# design.net
KiCad netlist of a schematic drawn in Altium Designer
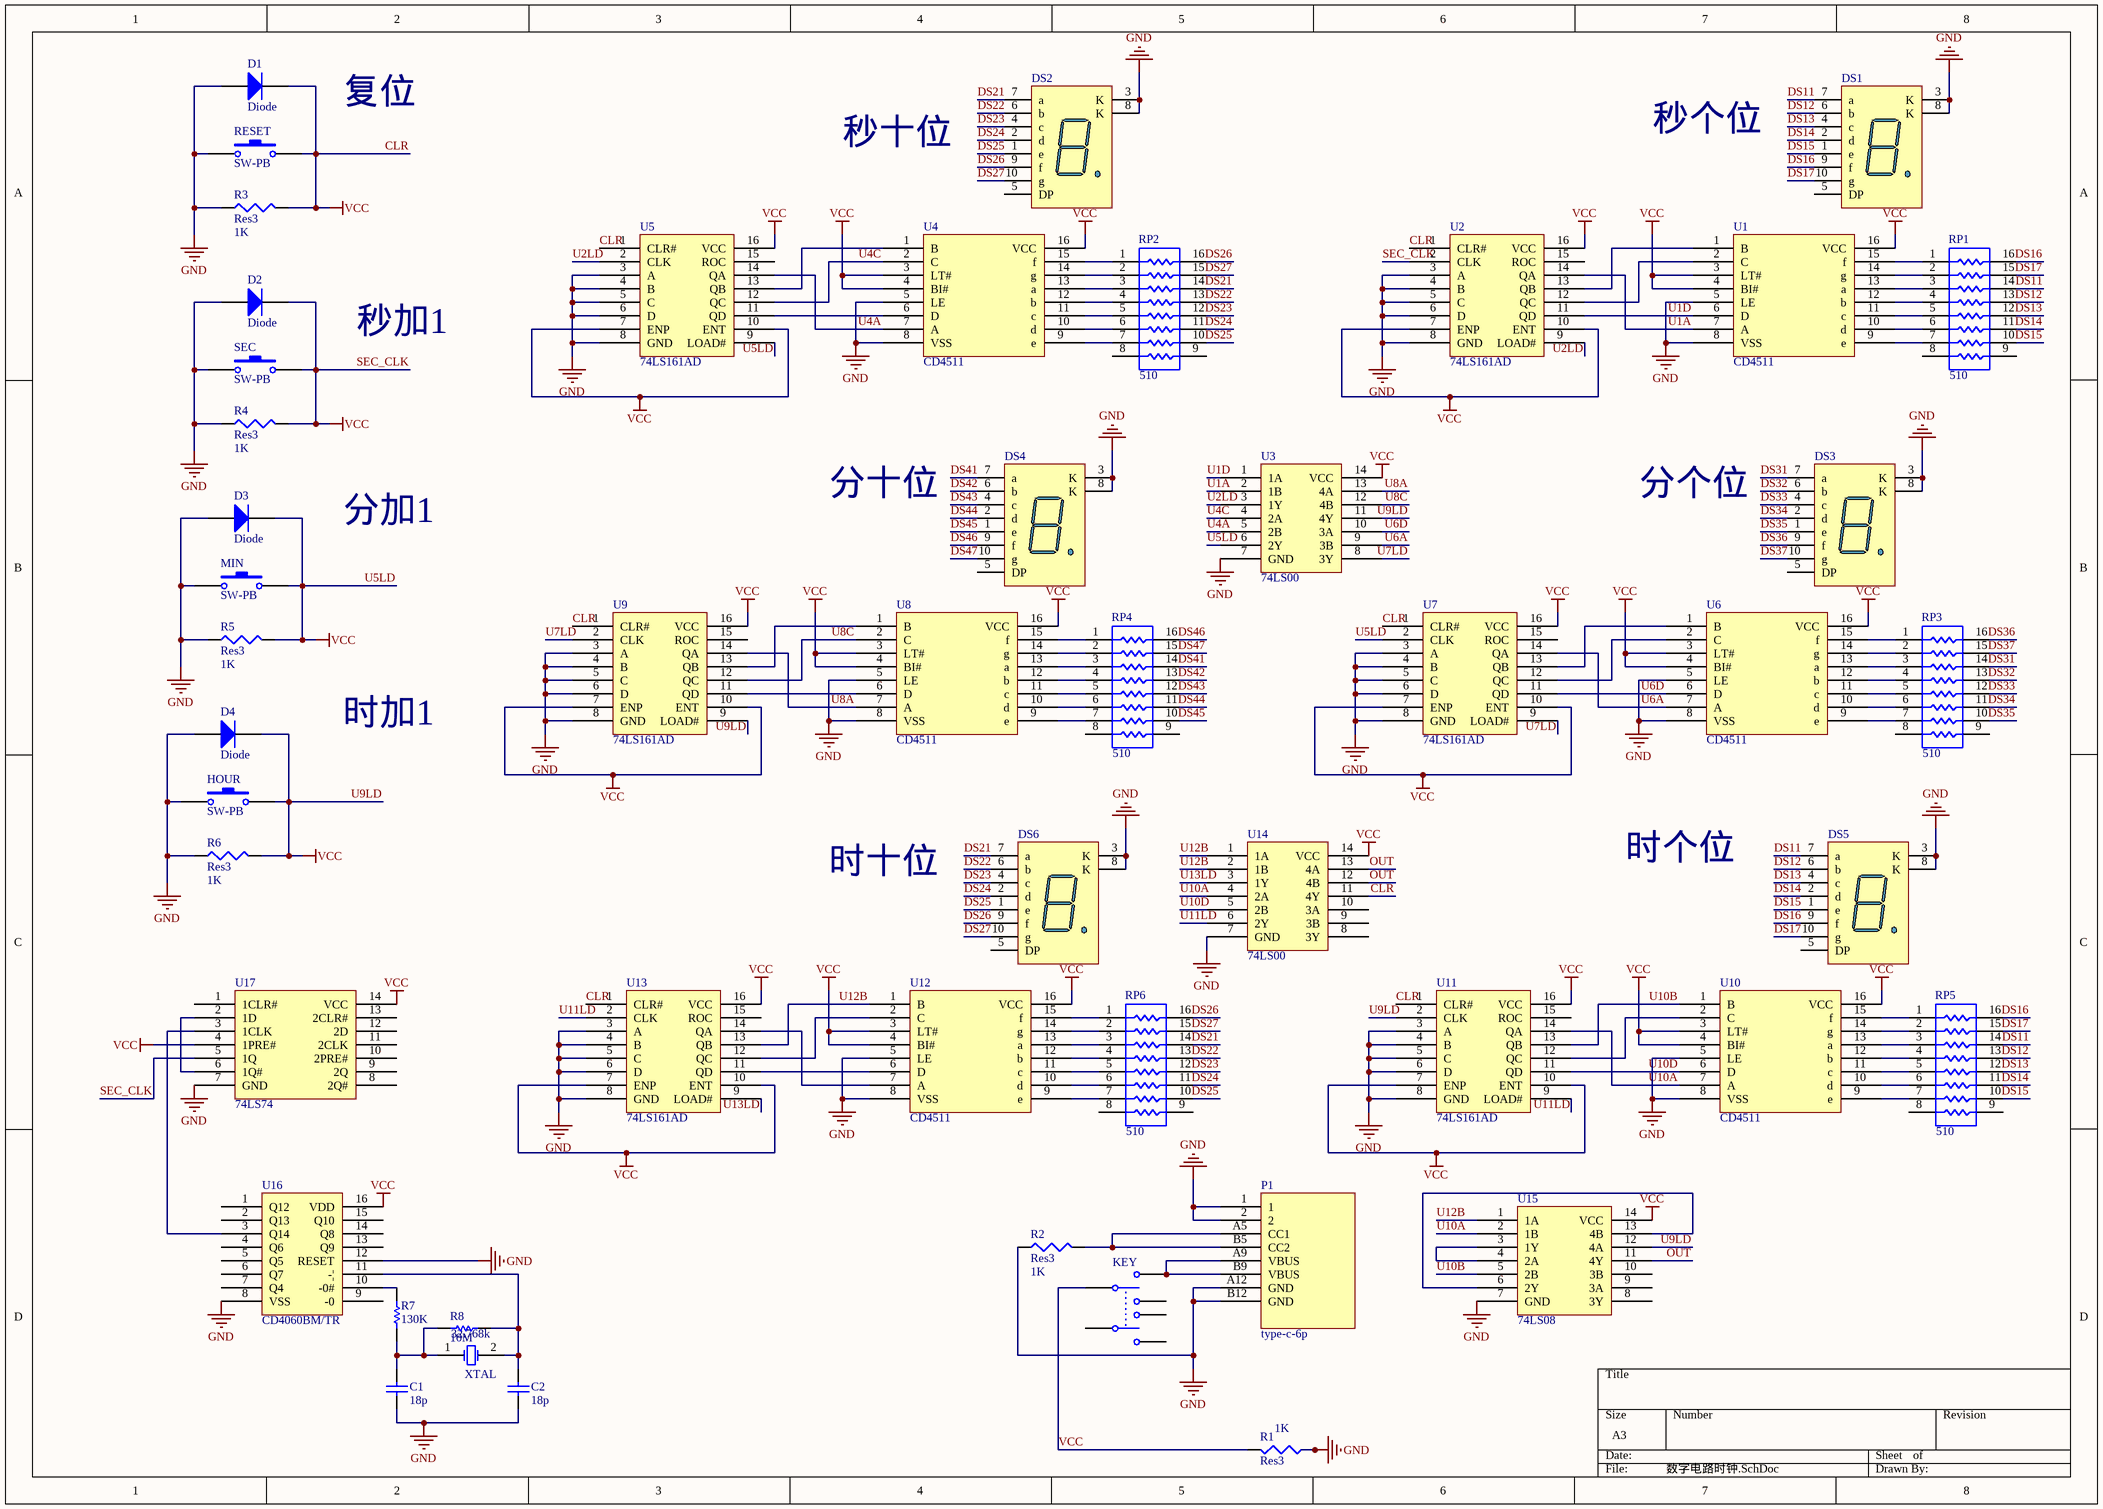
[diagram p0: 数字电路时钟.SchDoc]

(export (version "E")
  (design (tool "Eeschema 10.0.6"))
  (components
    (comp (ref "32.768k")
      (value "XTAL")
      (footprint "R38")
      (description "Crystal Oscillator")
      (fields (field (name "PUBLISHER") "Altium Limited"))
      (libsource (lib "Miscellaneous Devices") (part "XTAL"))
    )
    (comp (ref "C1")
      (value "18p")
      (footprint "C1206")
      (description "Capacitor (Semiconductor SIM Model)")
      (fields (field (name "Comment") "Cap Semi") (field (name "PUBLISHER") "Altium Limited"))
      (libsource (lib "Miscellaneous Devices") (part "Cap Semi"))
    )
    (comp (ref "C2")
      (value "18p")
      (footprint "C1206")
      (description "Capacitor (Semiconductor SIM Model)")
      (fields (field (name "Comment") "Cap Semi") (field (name "PUBLISHER") "Altium Limited"))
      (libsource (lib "Miscellaneous Devices") (part "Cap Semi"))
    )
    (comp (ref "D1")
      (value "Diode")
      (footprint "SMC")
      (description "Default Diode")
      (fields (field (name "PUBLISHER") "Altium Limited"))
      (libsource (lib "Miscellaneous Devices") (part "Diode"))
    )
    (comp (ref "D2")
      (value "Diode")
      (footprint "SMC")
      (description "Default Diode")
      (fields (field (name "PUBLISHER") "Altium Limited"))
      (libsource (lib "Miscellaneous Devices") (part "Diode"))
    )
    (comp (ref "D3")
      (value "Diode")
      (footprint "SMC")
      (description "Default Diode")
      (fields (field (name "PUBLISHER") "Altium Limited"))
      (libsource (lib "Miscellaneous Devices") (part "Diode"))
    )
    (comp (ref "D4")
      (value "Diode")
      (footprint "SMC")
      (description "Default Diode")
      (fields (field (name "PUBLISHER") "Altium Limited"))
      (libsource (lib "Miscellaneous Devices") (part "Diode"))
    )
    (comp (ref "DS1")
      (value "Dpy Blue-CC")
      (footprint "H")
      (description "14.2 mm General Purpose Blue 7-Segment Display: CC, RH DP, Gray Surface")
      (fields (field (name "PUBLISHER") "Altium Limited"))
      (libsource (lib "Miscellaneous Devices") (part "Dpy Blue-CC"))
    )
    (comp (ref "DS2")
      (value "Dpy Blue-CC")
      (footprint "H")
      (description "14.2 mm General Purpose Blue 7-Segment Display: CC, RH DP, Gray Surface")
      (fields (field (name "PUBLISHER") "Altium Limited"))
      (libsource (lib "Miscellaneous Devices") (part "Dpy Blue-CC"))
    )
    (comp (ref "DS3")
      (value "Dpy Blue-CC")
      (footprint "H")
      (description "14.2 mm General Purpose Blue 7-Segment Display: CC, RH DP, Gray Surface")
      (fields (field (name "PUBLISHER") "Altium Limited"))
      (libsource (lib "Miscellaneous Devices") (part "Dpy Blue-CC"))
    )
    (comp (ref "DS4")
      (value "Dpy Blue-CC")
      (footprint "H")
      (description "14.2 mm General Purpose Blue 7-Segment Display: CC, RH DP, Gray Surface")
      (fields (field (name "PUBLISHER") "Altium Limited"))
      (libsource (lib "Miscellaneous Devices") (part "Dpy Blue-CC"))
    )
    (comp (ref "DS5")
      (value "Dpy Blue-CC")
      (footprint "H")
      (description "14.2 mm General Purpose Blue 7-Segment Display: CC, RH DP, Gray Surface")
      (fields (field (name "PUBLISHER") "Altium Limited"))
      (libsource (lib "Miscellaneous Devices") (part "Dpy Blue-CC"))
    )
    (comp (ref "DS6")
      (value "Dpy Blue-CC")
      (footprint "H")
      (description "14.2 mm General Purpose Blue 7-Segment Display: CC, RH DP, Gray Surface")
      (fields (field (name "PUBLISHER") "Altium Limited"))
      (libsource (lib "Miscellaneous Devices") (part "Dpy Blue-CC"))
    )
    (comp (ref "HOUR")
      (value "SW-PB")
      (footprint "SPST-2")
      (description "Switch")
      (fields (field (name "PUBLISHER") "Altium Limited"))
      (libsource (lib "Miscellaneous Devices") (part "SW-PB"))
    )
    (comp (ref "KEY")
      (value "SW-DPDT")
      (footprint "SOT23-6_N")
      (description "Double-Pole, Double-Throw Switch")
      (fields (field (name "PUBLISHER") "Altium Limited"))
      (libsource (lib "Miscellaneous Devices") (part "SW-DPDT"))
    )
    (comp (ref "MIN")
      (value "SW-PB")
      (footprint "SPST-2")
      (description "Switch")
      (fields (field (name "PUBLISHER") "Altium Limited"))
      (libsource (lib "Miscellaneous Devices") (part "SW-PB"))
    )
    (comp (ref "P1")
      (value "type-c-6p")
      (footprint "type-c-6p - duplicate")
      (libsource (lib "数字时钟_课设") (part "type-c-6p"))
    )
    (comp (ref "R1")
      (value "Res3")
      (footprint "J1-0603")
      (description "Resistor")
      (fields (field (name "ALTIUM_VALUE") "1K") (field (name "PUBLISHER") "Altium Limited"))
      (libsource (lib "Miscellaneous Devices") (part "Res3"))
    )
    (comp (ref "R2")
      (value "Res3")
      (footprint "J1-0603")
      (description "Resistor")
      (fields (field (name "ALTIUM_VALUE") "1K") (field (name "PUBLISHER") "Altium Limited"))
      (libsource (lib "Miscellaneous Devices") (part "Res3"))
    )
    (comp (ref "R3")
      (value "Res3")
      (footprint "J1-0603")
      (description "Resistor")
      (fields (field (name "ALTIUM_VALUE") "1K") (field (name "PUBLISHER") "Altium Limited"))
      (libsource (lib "Miscellaneous Devices") (part "Res3"))
    )
    (comp (ref "R4")
      (value "Res3")
      (footprint "J1-0603")
      (description "Resistor")
      (fields (field (name "ALTIUM_VALUE") "1K") (field (name "PUBLISHER") "Altium Limited"))
      (libsource (lib "Miscellaneous Devices") (part "Res3"))
    )
    (comp (ref "R5")
      (value "Res3")
      (footprint "J1-0603")
      (description "Resistor")
      (fields (field (name "ALTIUM_VALUE") "1K") (field (name "PUBLISHER") "Altium Limited"))
      (libsource (lib "Miscellaneous Devices") (part "Res3"))
    )
    (comp (ref "R6")
      (value "Res3")
      (footprint "J1-0603")
      (description "Resistor")
      (fields (field (name "ALTIUM_VALUE") "1K") (field (name "PUBLISHER") "Altium Limited"))
      (libsource (lib "Miscellaneous Devices") (part "Res3"))
    )
    (comp (ref "R7")
      (value "130K")
      (footprint "AXIAL-0.3")
      (description "Resistor")
      (fields (field (name "Comment") "Res1") (field (name "PUBLISHER") "Altium Limited"))
      (libsource (lib "Miscellaneous Devices") (part "Res1"))
    )
    (comp (ref "R8")
      (value "10M")
      (footprint "AXIAL-0.3")
      (description "Resistor")
      (fields (field (name "Comment") "Res1") (field (name "PUBLISHER") "Altium Limited"))
      (libsource (lib "Miscellaneous Devices") (part "Res1"))
    )
    (comp (ref "RESET")
      (value "SW-PB")
      (footprint "SPST-2")
      (description "Switch")
      (fields (field (name "PUBLISHER") "Altium Limited"))
      (libsource (lib "Miscellaneous Devices") (part "SW-PB"))
    )
    (comp (ref "RP1")
      (value "510")
      (footprint "SO-16_N")
      (description "Isolated Resistor Network")
      (fields (field (name "Comment") "Res Pack3") (field (name "PUBLISHER") "Altium Limited"))
      (libsource (lib "Miscellaneous Devices") (part "Res Pack3"))
    )
    (comp (ref "RP2")
      (value "510")
      (footprint "SO-16_N")
      (description "Isolated Resistor Network")
      (fields (field (name "Comment") "Res Pack3") (field (name "PUBLISHER") "Altium Limited"))
      (libsource (lib "Miscellaneous Devices") (part "Res Pack3"))
    )
    (comp (ref "RP3")
      (value "510")
      (footprint "SO-16_N")
      (description "Isolated Resistor Network")
      (fields (field (name "Comment") "Res Pack3") (field (name "PUBLISHER") "Altium Limited"))
      (libsource (lib "Miscellaneous Devices") (part "Res Pack3"))
    )
    (comp (ref "RP4")
      (value "510")
      (footprint "SO-16_N")
      (description "Isolated Resistor Network")
      (fields (field (name "Comment") "Res Pack3") (field (name "PUBLISHER") "Altium Limited"))
      (libsource (lib "Miscellaneous Devices") (part "Res Pack3"))
    )
    (comp (ref "RP5")
      (value "510")
      (footprint "SO-16_N")
      (description "Isolated Resistor Network")
      (fields (field (name "Comment") "Res Pack3") (field (name "PUBLISHER") "Altium Limited"))
      (libsource (lib "Miscellaneous Devices") (part "Res Pack3"))
    )
    (comp (ref "RP6")
      (value "510")
      (footprint "SO-16_N")
      (description "Isolated Resistor Network")
      (fields (field (name "Comment") "Res Pack3") (field (name "PUBLISHER") "Altium Limited"))
      (libsource (lib "Miscellaneous Devices") (part "Res Pack3"))
    )
    (comp (ref "SEC")
      (value "SW-PB")
      (footprint "SPST-2")
      (description "Switch")
      (fields (field (name "PUBLISHER") "Altium Limited"))
      (libsource (lib "Miscellaneous Devices") (part "SW-PB"))
    )
    (comp (ref "U1") (value "CD4511") (footprint "CD4511BM/TR") (libsource (lib "数字电路时钟") (part "CD4511")))
    (comp (ref "U2") (value "74LS161AD") (footprint "74LS161") (libsource (lib "数字电路时钟") (part "74LS161AD")))
    (comp (ref "U3") (value "74LS00") (footprint "74LS00") (libsource (lib "数字电路时钟") (part "74LS00")))
    (comp (ref "U4") (value "CD4511") (footprint "CD4511BM/TR") (libsource (lib "数字电路时钟") (part "CD4511")))
    (comp (ref "U5") (value "74LS161AD") (footprint "74LS161") (libsource (lib "数字电路时钟") (part "74LS161AD")))
    (comp (ref "U6") (value "CD4511") (footprint "CD4511BM/TR") (libsource (lib "数字电路时钟") (part "CD4511")))
    (comp (ref "U7") (value "74LS161AD") (footprint "74LS161") (libsource (lib "数字电路时钟") (part "74LS161AD")))
    (comp (ref "U8") (value "CD4511") (footprint "CD4511BM/TR") (libsource (lib "数字电路时钟") (part "CD4511")))
    (comp (ref "U9") (value "74LS161AD") (footprint "74LS161") (libsource (lib "数字电路时钟") (part "74LS161AD")))
    (comp (ref "U10") (value "CD4511") (footprint "CD4511BM/TR") (libsource (lib "数字电路时钟") (part "CD4511")))
    (comp (ref "U11") (value "74LS161AD") (footprint "74LS161") (libsource (lib "数字电路时钟") (part "74LS161AD")))
    (comp (ref "U12") (value "CD4511") (footprint "CD4511BM/TR") (libsource (lib "数字电路时钟") (part "CD4511")))
    (comp (ref "U13") (value "74LS161AD") (footprint "74LS161") (libsource (lib "数字电路时钟") (part "74LS161AD")))
    (comp (ref "U14") (value "74LS00") (footprint "74LS00") (libsource (lib "数字电路时钟") (part "74LS00")))
    (comp (ref "U15") (value "74LS08") (footprint "74LS08") (libsource (lib "数字电路时钟") (part "74LS08")))
    (comp (ref "U16")
      (value "CD4060BM/TR")
      (footprint "CD4060BM/TR")
      (libsource (lib "数字电路时钟") (part "CD4060BM/TR"))
    )
    (comp (ref "U17") (value "74LS74") (footprint "74LS74") (libsource (lib "数字电路时钟") (part "74LS74")))
  )
  (nets
    (net (code "1") (name "/DS11") (class "Default")
      (node (ref "DS1") (pin "7") (pinfunction "a_7") (pintype "passive"))
      (node (ref "DS5") (pin "7") (pinfunction "a_7") (pintype "passive"))
      (node (ref "RP1") (pin "14") (pinfunction "14_14") (pintype "passive"))
      (node (ref "RP5") (pin "14") (pinfunction "14_14") (pintype "passive"))
    )
    (net (code "2") (name "/DS12") (class "Default")
      (node (ref "DS1") (pin "6") (pinfunction "b_6") (pintype "passive"))
      (node (ref "DS5") (pin "6") (pinfunction "b_6") (pintype "passive"))
      (node (ref "RP1") (pin "13") (pinfunction "13_13") (pintype "passive"))
      (node (ref "RP5") (pin "13") (pinfunction "13_13") (pintype "passive"))
    )
    (net (code "3") (name "/DS13") (class "Default")
      (node (ref "DS1") (pin "4") (pinfunction "c_4") (pintype "passive"))
      (node (ref "DS5") (pin "4") (pinfunction "c_4") (pintype "passive"))
      (node (ref "RP1") (pin "12") (pinfunction "12_12") (pintype "passive"))
      (node (ref "RP5") (pin "12") (pinfunction "12_12") (pintype "passive"))
    )
    (net (code "4") (name "/DS14") (class "Default")
      (node (ref "DS1") (pin "2") (pinfunction "d_2") (pintype "passive"))
      (node (ref "DS5") (pin "2") (pinfunction "d_2") (pintype "passive"))
      (node (ref "RP1") (pin "11") (pinfunction "11_11") (pintype "passive"))
      (node (ref "RP5") (pin "11") (pinfunction "11_11") (pintype "passive"))
    )
    (net (code "5") (name "/DS15") (class "Default")
      (node (ref "DS1") (pin "1") (pinfunction "e_1") (pintype "passive"))
      (node (ref "DS5") (pin "1") (pinfunction "e_1") (pintype "passive"))
      (node (ref "RP1") (pin "10") (pinfunction "10_10") (pintype "passive"))
      (node (ref "RP5") (pin "10") (pinfunction "10_10") (pintype "passive"))
    )
    (net (code "6") (name "/DS16") (class "Default")
      (node (ref "DS1") (pin "9") (pinfunction "f_9") (pintype "passive"))
      (node (ref "DS5") (pin "9") (pinfunction "f_9") (pintype "passive"))
      (node (ref "RP1") (pin "16") (pinfunction "16_16") (pintype "passive"))
      (node (ref "RP5") (pin "16") (pinfunction "16_16") (pintype "passive"))
    )
    (net (code "7") (name "/DS17") (class "Default")
      (node (ref "DS1") (pin "10") (pinfunction "g_10") (pintype "passive"))
      (node (ref "DS5") (pin "10") (pinfunction "g_10") (pintype "passive"))
      (node (ref "RP1") (pin "15") (pinfunction "15_15") (pintype "passive"))
      (node (ref "RP5") (pin "15") (pinfunction "15_15") (pintype "passive"))
    )
    (net (code "8") (name "/DS21") (class "Default")
      (node (ref "DS2") (pin "7") (pinfunction "a_7") (pintype "passive"))
      (node (ref "DS6") (pin "7") (pinfunction "a_7") (pintype "passive"))
      (node (ref "RP2") (pin "14") (pinfunction "14_14") (pintype "passive"))
      (node (ref "RP6") (pin "14") (pinfunction "14_14") (pintype "passive"))
    )
    (net (code "9") (name "/DS22") (class "Default")
      (node (ref "DS2") (pin "6") (pinfunction "b_6") (pintype "passive"))
      (node (ref "DS6") (pin "6") (pinfunction "b_6") (pintype "passive"))
      (node (ref "RP2") (pin "13") (pinfunction "13_13") (pintype "passive"))
      (node (ref "RP6") (pin "13") (pinfunction "13_13") (pintype "passive"))
    )
    (net (code "10") (name "/DS23") (class "Default")
      (node (ref "DS2") (pin "4") (pinfunction "c_4") (pintype "passive"))
      (node (ref "DS6") (pin "4") (pinfunction "c_4") (pintype "passive"))
      (node (ref "RP2") (pin "12") (pinfunction "12_12") (pintype "passive"))
      (node (ref "RP6") (pin "12") (pinfunction "12_12") (pintype "passive"))
    )
    (net (code "11") (name "/DS24") (class "Default")
      (node (ref "DS2") (pin "2") (pinfunction "d_2") (pintype "passive"))
      (node (ref "DS6") (pin "2") (pinfunction "d_2") (pintype "passive"))
      (node (ref "RP2") (pin "11") (pinfunction "11_11") (pintype "passive"))
      (node (ref "RP6") (pin "11") (pinfunction "11_11") (pintype "passive"))
    )
    (net (code "12") (name "/DS25") (class "Default")
      (node (ref "DS2") (pin "1") (pinfunction "e_1") (pintype "passive"))
      (node (ref "DS6") (pin "1") (pinfunction "e_1") (pintype "passive"))
      (node (ref "RP2") (pin "10") (pinfunction "10_10") (pintype "passive"))
      (node (ref "RP6") (pin "10") (pinfunction "10_10") (pintype "passive"))
    )
    (net (code "13") (name "/DS26") (class "Default")
      (node (ref "DS2") (pin "9") (pinfunction "f_9") (pintype "passive"))
      (node (ref "DS6") (pin "9") (pinfunction "f_9") (pintype "passive"))
      (node (ref "RP2") (pin "16") (pinfunction "16_16") (pintype "passive"))
      (node (ref "RP6") (pin "16") (pinfunction "16_16") (pintype "passive"))
    )
    (net (code "14") (name "/DS27") (class "Default")
      (node (ref "DS2") (pin "10") (pinfunction "g_10") (pintype "passive"))
      (node (ref "DS6") (pin "10") (pinfunction "g_10") (pintype "passive"))
      (node (ref "RP2") (pin "15") (pinfunction "15_15") (pintype "passive"))
      (node (ref "RP6") (pin "15") (pinfunction "15_15") (pintype "passive"))
    )
    (net (code "15") (name "/DS31") (class "Default")
      (node (ref "DS3") (pin "7") (pinfunction "a_7") (pintype "passive"))
      (node (ref "RP3") (pin "14") (pinfunction "14_14") (pintype "passive"))
    )
    (net (code "16") (name "/DS32") (class "Default")
      (node (ref "DS3") (pin "6") (pinfunction "b_6") (pintype "passive"))
      (node (ref "RP3") (pin "13") (pinfunction "13_13") (pintype "passive"))
    )
    (net (code "17") (name "/DS33") (class "Default")
      (node (ref "DS3") (pin "4") (pinfunction "c_4") (pintype "passive"))
      (node (ref "RP3") (pin "12") (pinfunction "12_12") (pintype "passive"))
    )
    (net (code "18") (name "/DS34") (class "Default")
      (node (ref "DS3") (pin "2") (pinfunction "d_2") (pintype "passive"))
      (node (ref "RP3") (pin "11") (pinfunction "11_11") (pintype "passive"))
    )
    (net (code "19") (name "/DS35") (class "Default")
      (node (ref "DS3") (pin "1") (pinfunction "e_1") (pintype "passive"))
      (node (ref "RP3") (pin "10") (pinfunction "10_10") (pintype "passive"))
    )
    (net (code "20") (name "/DS36") (class "Default")
      (node (ref "DS3") (pin "9") (pinfunction "f_9") (pintype "passive"))
      (node (ref "RP3") (pin "16") (pinfunction "16_16") (pintype "passive"))
    )
    (net (code "21") (name "/DS37") (class "Default")
      (node (ref "DS3") (pin "10") (pinfunction "g_10") (pintype "passive"))
      (node (ref "RP3") (pin "15") (pinfunction "15_15") (pintype "passive"))
    )
    (net (code "22") (name "/DS41") (class "Default")
      (node (ref "DS4") (pin "7") (pinfunction "a_7") (pintype "passive"))
      (node (ref "RP4") (pin "14") (pinfunction "14_14") (pintype "passive"))
    )
    (net (code "23") (name "/DS42") (class "Default")
      (node (ref "DS4") (pin "6") (pinfunction "b_6") (pintype "passive"))
      (node (ref "RP4") (pin "13") (pinfunction "13_13") (pintype "passive"))
    )
    (net (code "24") (name "/DS43") (class "Default")
      (node (ref "DS4") (pin "4") (pinfunction "c_4") (pintype "passive"))
      (node (ref "RP4") (pin "12") (pinfunction "12_12") (pintype "passive"))
    )
    (net (code "25") (name "/DS44") (class "Default")
      (node (ref "DS4") (pin "2") (pinfunction "d_2") (pintype "passive"))
      (node (ref "RP4") (pin "11") (pinfunction "11_11") (pintype "passive"))
    )
    (net (code "26") (name "/DS45") (class "Default")
      (node (ref "DS4") (pin "1") (pinfunction "e_1") (pintype "passive"))
      (node (ref "RP4") (pin "10") (pinfunction "10_10") (pintype "passive"))
    )
    (net (code "27") (name "/DS46") (class "Default")
      (node (ref "DS4") (pin "9") (pinfunction "f_9") (pintype "passive"))
      (node (ref "RP4") (pin "16") (pinfunction "16_16") (pintype "passive"))
    )
    (net (code "28") (name "/DS47") (class "Default")
      (node (ref "DS4") (pin "10") (pinfunction "g_10") (pintype "passive"))
      (node (ref "RP4") (pin "15") (pinfunction "15_15") (pintype "passive"))
    )
    (net (code "29") (name "/OUT") (class "Default")
      (node (ref "U14") (pin "12") (pinfunction "4B_12") (pintype "passive"))
      (node (ref "U14") (pin "13") (pinfunction "4A_13") (pintype "passive"))
      (node (ref "U15") (pin "11") (pinfunction "4Y_11") (pintype "passive"))
    )
    (net (code "30") (name "/U1A") (class "Default")
      (node (ref "U1") (pin "7") (pinfunction "A_7") (pintype "passive"))
      (node (ref "U2") (pin "14") (pinfunction "QA_14") (pintype "passive"))
      (node (ref "U3") (pin "2") (pinfunction "1B_2") (pintype "passive"))
    )
    (net (code "31") (name "/U1D") (class "Default")
      (node (ref "U1") (pin "6") (pinfunction "D_6") (pintype "passive"))
      (node (ref "U2") (pin "11") (pinfunction "QD_11") (pintype "passive"))
      (node (ref "U3") (pin "1") (pinfunction "1A_1") (pintype "passive"))
    )
    (net (code "32") (name "/U2LD") (class "Default")
      (node (ref "U2") (pin "9") (pinfunction "LOAD#_9") (pintype "passive"))
      (node (ref "U3") (pin "3") (pinfunction "1Y_3") (pintype "passive"))
      (node (ref "U5") (pin "2") (pinfunction "CLK_2") (pintype "passive"))
    )
    (net (code "33") (name "/U4A") (class "Default")
      (node (ref "U3") (pin "5") (pinfunction "2B_5") (pintype "passive"))
      (node (ref "U4") (pin "7") (pinfunction "A_7") (pintype "passive"))
      (node (ref "U5") (pin "14") (pinfunction "QA_14") (pintype "passive"))
    )
    (net (code "34") (name "/U4C") (class "Default")
      (node (ref "U3") (pin "4") (pinfunction "2A_4") (pintype "passive"))
      (node (ref "U4") (pin "2") (pinfunction "C_2") (pintype "passive"))
      (node (ref "U5") (pin "12") (pinfunction "QC_12") (pintype "passive"))
    )
    (net (code "35") (name "/U6A") (class "Default")
      (node (ref "U3") (pin "9") (pinfunction "3B_9") (pintype "passive"))
      (node (ref "U6") (pin "7") (pinfunction "A_7") (pintype "passive"))
      (node (ref "U7") (pin "14") (pinfunction "QA_14") (pintype "passive"))
    )
    (net (code "36") (name "/U6D") (class "Default")
      (node (ref "U3") (pin "10") (pinfunction "3A_10") (pintype "passive"))
      (node (ref "U6") (pin "6") (pinfunction "D_6") (pintype "passive"))
      (node (ref "U7") (pin "11") (pinfunction "QD_11") (pintype "passive"))
    )
    (net (code "37") (name "/U7LD") (class "Default")
      (node (ref "U3") (pin "8") (pinfunction "3Y_8") (pintype "passive"))
      (node (ref "U7") (pin "9") (pinfunction "LOAD#_9") (pintype "passive"))
      (node (ref "U9") (pin "2") (pinfunction "CLK_2") (pintype "passive"))
    )
    (net (code "38") (name "/U8A") (class "Default")
      (node (ref "U3") (pin "13") (pinfunction "4A_13") (pintype "passive"))
      (node (ref "U8") (pin "7") (pinfunction "A_7") (pintype "passive"))
      (node (ref "U9") (pin "14") (pinfunction "QA_14") (pintype "passive"))
    )
    (net (code "39") (name "/U8C") (class "Default")
      (node (ref "U3") (pin "12") (pinfunction "4B_12") (pintype "passive"))
      (node (ref "U8") (pin "2") (pinfunction "C_2") (pintype "passive"))
      (node (ref "U9") (pin "12") (pinfunction "QC_12") (pintype "passive"))
    )
    (net (code "40") (name "/U10A") (class "Default")
      (node (ref "U10") (pin "7") (pinfunction "A_7") (pintype "passive"))
      (node (ref "U11") (pin "14") (pinfunction "QA_14") (pintype "passive"))
      (node (ref "U14") (pin "4") (pinfunction "2A_4") (pintype "passive"))
      (node (ref "U15") (pin "2") (pinfunction "1B_2") (pintype "passive"))
    )
    (net (code "41") (name "/U10B") (class "Default")
      (node (ref "U10") (pin "1") (pinfunction "B_1") (pintype "passive"))
      (node (ref "U11") (pin "13") (pinfunction "QB_13") (pintype "passive"))
      (node (ref "U15") (pin "5") (pinfunction "2B_5") (pintype "passive"))
    )
    (net (code "42") (name "/U10D") (class "Default")
      (node (ref "U10") (pin "6") (pinfunction "D_6") (pintype "passive"))
      (node (ref "U11") (pin "11") (pinfunction "QD_11") (pintype "passive"))
      (node (ref "U14") (pin "5") (pinfunction "2B_5") (pintype "passive"))
    )
    (net (code "43") (name "/U11LD") (class "Default")
      (node (ref "U11") (pin "9") (pinfunction "LOAD#_9") (pintype "passive"))
      (node (ref "U13") (pin "2") (pinfunction "CLK_2") (pintype "passive"))
      (node (ref "U14") (pin "6") (pinfunction "2Y_6") (pintype "passive"))
    )
    (net (code "44") (name "/U12B") (class "Default")
      (node (ref "U12") (pin "1") (pinfunction "B_1") (pintype "passive"))
      (node (ref "U13") (pin "13") (pinfunction "QB_13") (pintype "passive"))
      (node (ref "U14") (pin "1") (pinfunction "1A_1") (pintype "passive"))
      (node (ref "U14") (pin "2") (pinfunction "1B_2") (pintype "passive"))
      (node (ref "U15") (pin "1") (pinfunction "1A_1") (pintype "passive"))
    )
    (net (code "45") (name "/U13LD") (class "Default")
      (node (ref "U13") (pin "9") (pinfunction "LOAD#_9") (pintype "passive"))
      (node (ref "U14") (pin "3") (pinfunction "1Y_3") (pintype "passive"))
    )
    (net (code "46") (name "GND") (class "Default")
      (node (ref "C1") (pin "1") (pinfunction "1_1") (pintype "passive"))
      (node (ref "C2") (pin "1") (pinfunction "1_1") (pintype "passive"))
      (node (ref "D1") (pin "1") (pinfunction "A_1") (pintype "passive"))
      (node (ref "D2") (pin "1") (pinfunction "A_1") (pintype "passive"))
      (node (ref "D3") (pin "1") (pinfunction "A_1") (pintype "passive"))
      (node (ref "D4") (pin "1") (pinfunction "A_1") (pintype "passive"))
      (node (ref "DS1") (pin "3") (pinfunction "K_3") (pintype "passive"))
      (node (ref "DS1") (pin "8") (pinfunction "K_8") (pintype "passive"))
      (node (ref "DS2") (pin "3") (pinfunction "K_3") (pintype "passive"))
      (node (ref "DS2") (pin "8") (pinfunction "K_8") (pintype "passive"))
      (node (ref "DS3") (pin "3") (pinfunction "K_3") (pintype "passive"))
      (node (ref "DS3") (pin "8") (pinfunction "K_8") (pintype "passive"))
      (node (ref "DS4") (pin "3") (pinfunction "K_3") (pintype "passive"))
      (node (ref "DS4") (pin "8") (pinfunction "K_8") (pintype "passive"))
      (node (ref "DS5") (pin "3") (pinfunction "K_3") (pintype "passive"))
      (node (ref "DS5") (pin "8") (pinfunction "K_8") (pintype "passive"))
      (node (ref "DS6") (pin "3") (pinfunction "K_3") (pintype "passive"))
      (node (ref "DS6") (pin "8") (pinfunction "K_8") (pintype "passive"))
      (node (ref "HOUR") (pin "1") (pinfunction "1_1") (pintype "passive"))
      (node (ref "MIN") (pin "1") (pinfunction "1_1") (pintype "passive"))
      (node (ref "P1") (pin "1") (pinfunction "1_1") (pintype "passive"))
      (node (ref "P1") (pin "2") (pinfunction "2_2") (pintype "passive"))
      (node (ref "P1") (pin "A12") (pinfunction "GND_A12") (pintype "passive"))
      (node (ref "P1") (pin "B12") (pinfunction "GND_B12") (pintype "passive"))
      (node (ref "R1") (pin "1") (pinfunction "1_1") (pintype "passive"))
      (node (ref "R2") (pin "1") (pinfunction "1_1") (pintype "passive"))
      (node (ref "R3") (pin "1") (pinfunction "1_1") (pintype "passive"))
      (node (ref "R4") (pin "1") (pinfunction "1_1") (pintype "passive"))
      (node (ref "R5") (pin "1") (pinfunction "1_1") (pintype "passive"))
      (node (ref "R6") (pin "1") (pinfunction "1_1") (pintype "passive"))
      (node (ref "RESET") (pin "1") (pinfunction "1_1") (pintype "passive"))
      (node (ref "SEC") (pin "1") (pinfunction "1_1") (pintype "passive"))
      (node (ref "U1") (pin "5") (pinfunction "LE_5") (pintype "passive"))
      (node (ref "U1") (pin "8") (pinfunction "VSS_8") (pintype "passive"))
      (node (ref "U10") (pin "5") (pinfunction "LE_5") (pintype "passive"))
      (node (ref "U10") (pin "8") (pinfunction "VSS_8") (pintype "passive"))
      (node (ref "U11") (pin "3") (pinfunction "A_3") (pintype "passive"))
      (node (ref "U11") (pin "4") (pinfunction "B_4") (pintype "passive"))
      (node (ref "U11") (pin "5") (pinfunction "C_5") (pintype "passive"))
      (node (ref "U11") (pin "6") (pinfunction "D_6") (pintype "passive"))
      (node (ref "U11") (pin "8") (pinfunction "GND_8") (pintype "passive"))
      (node (ref "U12") (pin "5") (pinfunction "LE_5") (pintype "passive"))
      (node (ref "U12") (pin "8") (pinfunction "VSS_8") (pintype "passive"))
      (node (ref "U13") (pin "3") (pinfunction "A_3") (pintype "passive"))
      (node (ref "U13") (pin "4") (pinfunction "B_4") (pintype "passive"))
      (node (ref "U13") (pin "5") (pinfunction "C_5") (pintype "passive"))
      (node (ref "U13") (pin "6") (pinfunction "D_6") (pintype "passive"))
      (node (ref "U13") (pin "8") (pinfunction "GND_8") (pintype "passive"))
      (node (ref "U14") (pin "7") (pinfunction "GND_7") (pintype "passive"))
      (node (ref "U15") (pin "7") (pinfunction "GND_7") (pintype "passive"))
      (node (ref "U16") (pin "12") (pinfunction "RESET_12") (pintype "passive"))
      (node (ref "U16") (pin "8") (pinfunction "VSS_8") (pintype "passive"))
      (node (ref "U17") (pin "7") (pinfunction "GND_7") (pintype "passive"))
      (node (ref "U2") (pin "3") (pinfunction "A_3") (pintype "passive"))
      (node (ref "U2") (pin "4") (pinfunction "B_4") (pintype "passive"))
      (node (ref "U2") (pin "5") (pinfunction "C_5") (pintype "passive"))
      (node (ref "U2") (pin "6") (pinfunction "D_6") (pintype "passive"))
      (node (ref "U2") (pin "8") (pinfunction "GND_8") (pintype "passive"))
      (node (ref "U3") (pin "7") (pinfunction "GND_7") (pintype "passive"))
      (node (ref "U4") (pin "5") (pinfunction "LE_5") (pintype "passive"))
      (node (ref "U4") (pin "8") (pinfunction "VSS_8") (pintype "passive"))
      (node (ref "U5") (pin "3") (pinfunction "A_3") (pintype "passive"))
      (node (ref "U5") (pin "4") (pinfunction "B_4") (pintype "passive"))
      (node (ref "U5") (pin "5") (pinfunction "C_5") (pintype "passive"))
      (node (ref "U5") (pin "6") (pinfunction "D_6") (pintype "passive"))
      (node (ref "U5") (pin "8") (pinfunction "GND_8") (pintype "passive"))
      (node (ref "U6") (pin "5") (pinfunction "LE_5") (pintype "passive"))
      (node (ref "U6") (pin "8") (pinfunction "VSS_8") (pintype "passive"))
      (node (ref "U7") (pin "3") (pinfunction "A_3") (pintype "passive"))
      (node (ref "U7") (pin "4") (pinfunction "B_4") (pintype "passive"))
      (node (ref "U7") (pin "5") (pinfunction "C_5") (pintype "passive"))
      (node (ref "U7") (pin "6") (pinfunction "D_6") (pintype "passive"))
      (node (ref "U7") (pin "8") (pinfunction "GND_8") (pintype "passive"))
      (node (ref "U8") (pin "5") (pinfunction "LE_5") (pintype "passive"))
      (node (ref "U8") (pin "8") (pinfunction "VSS_8") (pintype "passive"))
      (node (ref "U9") (pin "3") (pinfunction "A_3") (pintype "passive"))
      (node (ref "U9") (pin "4") (pinfunction "B_4") (pintype "passive"))
      (node (ref "U9") (pin "5") (pinfunction "C_5") (pintype "passive"))
      (node (ref "U9") (pin "6") (pinfunction "D_6") (pintype "passive"))
      (node (ref "U9") (pin "8") (pinfunction "GND_8") (pintype "passive"))
    )
    (net (code "47") (name "Net-(32.768k-OSC1)") (class "Default")
      (node (ref "32.768k") (pin "1") (pinfunction "OSC1_1") (pintype "passive"))
      (node (ref "C1") (pin "2") (pinfunction "2_2") (pintype "passive"))
      (node (ref "R7") (pin "2") (pinfunction "2_2") (pintype "passive"))
      (node (ref "R8") (pin "1") (pinfunction "1_1") (pintype "passive"))
    )
    (net (code "48") (name "Net-(32.768k-OSC2)") (class "Default")
      (node (ref "32.768k") (pin "2") (pinfunction "OSC2_2") (pintype "passive"))
      (node (ref "C2") (pin "2") (pinfunction "2_2") (pintype "passive"))
      (node (ref "R8") (pin "2") (pinfunction "2_2") (pintype "passive"))
      (node (ref "U16") (pin "11") (pinfunction "-¦_11") (pintype "passive"))
    )
    (net (code "49") (name "Net-(KEY-Pad2)") (class "Default")
      (node (ref "KEY") (pin "2") (pinfunction "2_2") (pintype "passive"))
      (node (ref "P1") (pin "A9") (pinfunction "VBUS_A9") (pintype "passive"))
      (node (ref "P1") (pin "B9") (pinfunction "VBUS_B9") (pintype "passive"))
    )
    (net (code "50") (name "Net-(P1-CC1)") (class "Default")
      (node (ref "P1") (pin "A5") (pinfunction "CC1_A5") (pintype "passive"))
      (node (ref "P1") (pin "B5") (pinfunction "CC2_B5") (pintype "passive"))
      (node (ref "R2") (pin "2") (pinfunction "2_2") (pintype "passive"))
    )
    (net (code "51") (name "Net-(U1-B)") (class "Default")
      (node (ref "U1") (pin "1") (pinfunction "B_1") (pintype "passive"))
      (node (ref "U2") (pin "13") (pinfunction "QB_13") (pintype "passive"))
    )
    (net (code "52") (name "Net-(U1-C)") (class "Default")
      (node (ref "U1") (pin "2") (pinfunction "C_2") (pintype "passive"))
      (node (ref "U2") (pin "12") (pinfunction "QC_12") (pintype "passive"))
    )
    (net (code "53") (name "Net-(U1-a)") (class "Default")
      (node (ref "RP1") (pin "3") (pinfunction "3_3") (pintype "passive"))
      (node (ref "U1") (pin "13") (pinfunction "a_13") (pintype "passive"))
    )
    (net (code "54") (name "Net-(U1-b)") (class "Default")
      (node (ref "RP1") (pin "4") (pinfunction "4_4") (pintype "passive"))
      (node (ref "U1") (pin "12") (pinfunction "b_12") (pintype "passive"))
    )
    (net (code "55") (name "Net-(U1-c)") (class "Default")
      (node (ref "RP1") (pin "5") (pinfunction "5_5") (pintype "passive"))
      (node (ref "U1") (pin "11") (pinfunction "c_11") (pintype "passive"))
    )
    (net (code "56") (name "Net-(U1-d)") (class "Default")
      (node (ref "RP1") (pin "6") (pinfunction "6_6") (pintype "passive"))
      (node (ref "U1") (pin "10") (pinfunction "d_10") (pintype "passive"))
    )
    (net (code "57") (name "Net-(U1-e)") (class "Default")
      (node (ref "RP1") (pin "7") (pinfunction "7_7") (pintype "passive"))
      (node (ref "U1") (pin "9") (pinfunction "e_9") (pintype "passive"))
    )
    (net (code "58") (name "Net-(U1-f)") (class "Default")
      (node (ref "RP1") (pin "1") (pinfunction "1_1") (pintype "passive"))
      (node (ref "U1") (pin "15") (pinfunction "f_15") (pintype "passive"))
    )
    (net (code "59") (name "Net-(U1-g)") (class "Default")
      (node (ref "RP1") (pin "2") (pinfunction "2_2") (pintype "passive"))
      (node (ref "U1") (pin "14") (pinfunction "g_14") (pintype "passive"))
    )
    (net (code "60") (name "Net-(U4-B)") (class "Default")
      (node (ref "U4") (pin "1") (pinfunction "B_1") (pintype "passive"))
      (node (ref "U5") (pin "13") (pinfunction "QB_13") (pintype "passive"))
    )
    (net (code "61") (name "Net-(U4-D)") (class "Default")
      (node (ref "U4") (pin "6") (pinfunction "D_6") (pintype "passive"))
      (node (ref "U5") (pin "11") (pinfunction "QD_11") (pintype "passive"))
    )
    (net (code "62") (name "Net-(U4-a)") (class "Default")
      (node (ref "RP2") (pin "3") (pinfunction "3_3") (pintype "passive"))
      (node (ref "U4") (pin "13") (pinfunction "a_13") (pintype "passive"))
    )
    (net (code "63") (name "Net-(U4-b)") (class "Default")
      (node (ref "RP2") (pin "4") (pinfunction "4_4") (pintype "passive"))
      (node (ref "U4") (pin "12") (pinfunction "b_12") (pintype "passive"))
    )
    (net (code "64") (name "Net-(U4-c)") (class "Default")
      (node (ref "RP2") (pin "5") (pinfunction "5_5") (pintype "passive"))
      (node (ref "U4") (pin "11") (pinfunction "c_11") (pintype "passive"))
    )
    (net (code "65") (name "Net-(U4-d)") (class "Default")
      (node (ref "RP2") (pin "6") (pinfunction "6_6") (pintype "passive"))
      (node (ref "U4") (pin "10") (pinfunction "d_10") (pintype "passive"))
    )
    (net (code "66") (name "Net-(U4-e)") (class "Default")
      (node (ref "RP2") (pin "7") (pinfunction "7_7") (pintype "passive"))
      (node (ref "U4") (pin "9") (pinfunction "e_9") (pintype "passive"))
    )
    (net (code "67") (name "Net-(U4-f)") (class "Default")
      (node (ref "RP2") (pin "1") (pinfunction "1_1") (pintype "passive"))
      (node (ref "U4") (pin "15") (pinfunction "f_15") (pintype "passive"))
    )
    (net (code "68") (name "Net-(U4-g)") (class "Default")
      (node (ref "RP2") (pin "2") (pinfunction "2_2") (pintype "passive"))
      (node (ref "U4") (pin "14") (pinfunction "g_14") (pintype "passive"))
    )
    (net (code "69") (name "Net-(U6-B)") (class "Default")
      (node (ref "U6") (pin "1") (pinfunction "B_1") (pintype "passive"))
      (node (ref "U7") (pin "13") (pinfunction "QB_13") (pintype "passive"))
    )
    (net (code "70") (name "Net-(U6-C)") (class "Default")
      (node (ref "U6") (pin "2") (pinfunction "C_2") (pintype "passive"))
      (node (ref "U7") (pin "12") (pinfunction "QC_12") (pintype "passive"))
    )
    (net (code "71") (name "Net-(U6-a)") (class "Default")
      (node (ref "RP3") (pin "3") (pinfunction "3_3") (pintype "passive"))
      (node (ref "U6") (pin "13") (pinfunction "a_13") (pintype "passive"))
    )
    (net (code "72") (name "Net-(U6-b)") (class "Default")
      (node (ref "RP3") (pin "4") (pinfunction "4_4") (pintype "passive"))
      (node (ref "U6") (pin "12") (pinfunction "b_12") (pintype "passive"))
    )
    (net (code "73") (name "Net-(U6-c)") (class "Default")
      (node (ref "RP3") (pin "5") (pinfunction "5_5") (pintype "passive"))
      (node (ref "U6") (pin "11") (pinfunction "c_11") (pintype "passive"))
    )
    (net (code "74") (name "Net-(U6-d)") (class "Default")
      (node (ref "RP3") (pin "6") (pinfunction "6_6") (pintype "passive"))
      (node (ref "U6") (pin "10") (pinfunction "d_10") (pintype "passive"))
    )
    (net (code "75") (name "Net-(U6-e)") (class "Default")
      (node (ref "RP3") (pin "7") (pinfunction "7_7") (pintype "passive"))
      (node (ref "U6") (pin "9") (pinfunction "e_9") (pintype "passive"))
    )
    (net (code "76") (name "Net-(U6-f)") (class "Default")
      (node (ref "RP3") (pin "1") (pinfunction "1_1") (pintype "passive"))
      (node (ref "U6") (pin "15") (pinfunction "f_15") (pintype "passive"))
    )
    (net (code "77") (name "Net-(U6-g)") (class "Default")
      (node (ref "RP3") (pin "2") (pinfunction "2_2") (pintype "passive"))
      (node (ref "U6") (pin "14") (pinfunction "g_14") (pintype "passive"))
    )
    (net (code "78") (name "Net-(U8-B)") (class "Default")
      (node (ref "U8") (pin "1") (pinfunction "B_1") (pintype "passive"))
      (node (ref "U9") (pin "13") (pinfunction "QB_13") (pintype "passive"))
    )
    (net (code "79") (name "Net-(U8-D)") (class "Default")
      (node (ref "U8") (pin "6") (pinfunction "D_6") (pintype "passive"))
      (node (ref "U9") (pin "11") (pinfunction "QD_11") (pintype "passive"))
    )
    (net (code "80") (name "Net-(U8-a)") (class "Default")
      (node (ref "RP4") (pin "3") (pinfunction "3_3") (pintype "passive"))
      (node (ref "U8") (pin "13") (pinfunction "a_13") (pintype "passive"))
    )
    (net (code "81") (name "Net-(U8-b)") (class "Default")
      (node (ref "RP4") (pin "4") (pinfunction "4_4") (pintype "passive"))
      (node (ref "U8") (pin "12") (pinfunction "b_12") (pintype "passive"))
    )
    (net (code "82") (name "Net-(U8-c)") (class "Default")
      (node (ref "RP4") (pin "5") (pinfunction "5_5") (pintype "passive"))
      (node (ref "U8") (pin "11") (pinfunction "c_11") (pintype "passive"))
    )
    (net (code "83") (name "Net-(U8-d)") (class "Default")
      (node (ref "RP4") (pin "6") (pinfunction "6_6") (pintype "passive"))
      (node (ref "U8") (pin "10") (pinfunction "d_10") (pintype "passive"))
    )
    (net (code "84") (name "Net-(U8-e)") (class "Default")
      (node (ref "RP4") (pin "7") (pinfunction "7_7") (pintype "passive"))
      (node (ref "U8") (pin "9") (pinfunction "e_9") (pintype "passive"))
    )
    (net (code "85") (name "Net-(U8-f)") (class "Default")
      (node (ref "RP4") (pin "1") (pinfunction "1_1") (pintype "passive"))
      (node (ref "U8") (pin "15") (pinfunction "f_15") (pintype "passive"))
    )
    (net (code "86") (name "Net-(U8-g)") (class "Default")
      (node (ref "RP4") (pin "2") (pinfunction "2_2") (pintype "passive"))
      (node (ref "U8") (pin "14") (pinfunction "g_14") (pintype "passive"))
    )
    (net (code "87") (name "Net-(U10-C)") (class "Default")
      (node (ref "U10") (pin "2") (pinfunction "C_2") (pintype "passive"))
      (node (ref "U11") (pin "12") (pinfunction "QC_12") (pintype "passive"))
    )
    (net (code "88") (name "Net-(U10-a)") (class "Default")
      (node (ref "RP5") (pin "3") (pinfunction "3_3") (pintype "passive"))
      (node (ref "U10") (pin "13") (pinfunction "a_13") (pintype "passive"))
    )
    (net (code "89") (name "Net-(U10-b)") (class "Default")
      (node (ref "RP5") (pin "4") (pinfunction "4_4") (pintype "passive"))
      (node (ref "U10") (pin "12") (pinfunction "b_12") (pintype "passive"))
    )
    (net (code "90") (name "Net-(U10-c)") (class "Default")
      (node (ref "RP5") (pin "5") (pinfunction "5_5") (pintype "passive"))
      (node (ref "U10") (pin "11") (pinfunction "c_11") (pintype "passive"))
    )
    (net (code "91") (name "Net-(U10-d)") (class "Default")
      (node (ref "RP5") (pin "6") (pinfunction "6_6") (pintype "passive"))
      (node (ref "U10") (pin "10") (pinfunction "d_10") (pintype "passive"))
    )
    (net (code "92") (name "Net-(U10-e)") (class "Default")
      (node (ref "RP5") (pin "7") (pinfunction "7_7") (pintype "passive"))
      (node (ref "U10") (pin "9") (pinfunction "e_9") (pintype "passive"))
    )
    (net (code "93") (name "Net-(U10-f)") (class "Default")
      (node (ref "RP5") (pin "1") (pinfunction "1_1") (pintype "passive"))
      (node (ref "U10") (pin "15") (pinfunction "f_15") (pintype "passive"))
    )
    (net (code "94") (name "Net-(U10-g)") (class "Default")
      (node (ref "RP5") (pin "2") (pinfunction "2_2") (pintype "passive"))
      (node (ref "U10") (pin "14") (pinfunction "g_14") (pintype "passive"))
    )
    (net (code "95") (name "Net-(U12-A)") (class "Default")
      (node (ref "U12") (pin "7") (pinfunction "A_7") (pintype "passive"))
      (node (ref "U13") (pin "14") (pinfunction "QA_14") (pintype "passive"))
    )
    (net (code "96") (name "Net-(U12-C)") (class "Default")
      (node (ref "U12") (pin "2") (pinfunction "C_2") (pintype "passive"))
      (node (ref "U13") (pin "12") (pinfunction "QC_12") (pintype "passive"))
    )
    (net (code "97") (name "Net-(U12-D)") (class "Default")
      (node (ref "U12") (pin "6") (pinfunction "D_6") (pintype "passive"))
      (node (ref "U13") (pin "11") (pinfunction "QD_11") (pintype "passive"))
    )
    (net (code "98") (name "Net-(U12-a)") (class "Default")
      (node (ref "RP6") (pin "3") (pinfunction "3_3") (pintype "passive"))
      (node (ref "U12") (pin "13") (pinfunction "a_13") (pintype "passive"))
    )
    (net (code "99") (name "Net-(U12-b)") (class "Default")
      (node (ref "RP6") (pin "4") (pinfunction "4_4") (pintype "passive"))
      (node (ref "U12") (pin "12") (pinfunction "b_12") (pintype "passive"))
    )
    (net (code "100") (name "Net-(U12-c)") (class "Default")
      (node (ref "RP6") (pin "5") (pinfunction "5_5") (pintype "passive"))
      (node (ref "U12") (pin "11") (pinfunction "c_11") (pintype "passive"))
    )
    (net (code "101") (name "Net-(U12-d)") (class "Default")
      (node (ref "RP6") (pin "6") (pinfunction "6_6") (pintype "passive"))
      (node (ref "U12") (pin "10") (pinfunction "d_10") (pintype "passive"))
    )
    (net (code "102") (name "Net-(U12-e)") (class "Default")
      (node (ref "RP6") (pin "7") (pinfunction "7_7") (pintype "passive"))
      (node (ref "U12") (pin "9") (pinfunction "e_9") (pintype "passive"))
    )
    (net (code "103") (name "Net-(U12-f)") (class "Default")
      (node (ref "RP6") (pin "1") (pinfunction "1_1") (pintype "passive"))
      (node (ref "U12") (pin "15") (pinfunction "f_15") (pintype "passive"))
    )
    (net (code "104") (name "Net-(U12-g)") (class "Default")
      (node (ref "RP6") (pin "2") (pinfunction "2_2") (pintype "passive"))
      (node (ref "U12") (pin "14") (pinfunction "g_14") (pintype "passive"))
    )
    (net (code "105") (name "Net-(U15-1Y)") (class "Default")
      (node (ref "U15") (pin "3") (pinfunction "1Y_3") (pintype "passive"))
      (node (ref "U15") (pin "4") (pinfunction "2A_4") (pintype "passive"))
    )
    (net (code "106") (name "Net-(U15-2Y)") (class "Default")
      (node (ref "U15") (pin "13") (pinfunction "4B_13") (pintype "passive"))
      (node (ref "U15") (pin "6") (pinfunction "2Y_6") (pintype "passive"))
    )
    (net (code "107") (name "Net-(U16--0#)") (class "Default")
      (node (ref "R7") (pin "1") (pinfunction "1_1") (pintype "passive"))
      (node (ref "U16") (pin "10") (pinfunction "-0#_10") (pintype "passive"))
    )
    (net (code "108") (name "Net-(U16-Q14)") (class "Default")
      (node (ref "U16") (pin "3") (pinfunction "Q14_3") (pintype "passive"))
      (node (ref "U17") (pin "3") (pinfunction "1CLK_3") (pintype "passive"))
    )
    (net (code "109") (name "Net-(U17-1D)") (class "Default")
      (node (ref "U17") (pin "2") (pinfunction "1D_2") (pintype "passive"))
      (node (ref "U17") (pin "6") (pinfunction "1Q#_6") (pintype "passive"))
    )
    (net (code "110") (name "VCC") (class "Default")
      (node (ref "D1") (pin "2") (pinfunction "K_2") (pintype "passive"))
      (node (ref "D2") (pin "2") (pinfunction "K_2") (pintype "passive"))
      (node (ref "D3") (pin "2") (pinfunction "K_2") (pintype "passive"))
      (node (ref "D4") (pin "2") (pinfunction "K_2") (pintype "passive"))
      (node (ref "HOUR") (pin "2") (pinfunction "2_2") (pintype "passive"))
      (node (ref "KEY") (pin "1") (pinfunction "1_1") (pintype "passive"))
      (node (ref "MIN") (pin "2") (pinfunction "2_2") (pintype "passive"))
      (node (ref "R1") (pin "2") (pinfunction "2_2") (pintype "passive"))
      (node (ref "R3") (pin "2") (pinfunction "2_2") (pintype "passive"))
      (node (ref "R4") (pin "2") (pinfunction "2_2") (pintype "passive"))
      (node (ref "R5") (pin "2") (pinfunction "2_2") (pintype "passive"))
      (node (ref "R6") (pin "2") (pinfunction "2_2") (pintype "passive"))
      (node (ref "RESET") (pin "2") (pinfunction "2_2") (pintype "passive"))
      (node (ref "SEC") (pin "2") (pinfunction "2_2") (pintype "passive"))
      (node (ref "U1") (pin "16") (pinfunction "VCC_16") (pintype "passive"))
      (node (ref "U1") (pin "3") (pinfunction "LT#_3") (pintype "passive"))
      (node (ref "U1") (pin "4") (pinfunction "BI#_4") (pintype "passive"))
      (node (ref "U10") (pin "16") (pinfunction "VCC_16") (pintype "passive"))
      (node (ref "U10") (pin "3") (pinfunction "LT#_3") (pintype "passive"))
      (node (ref "U10") (pin "4") (pinfunction "BI#_4") (pintype "passive"))
      (node (ref "U11") (pin "1") (pinfunction "CLR#_1") (pintype "passive"))
      (node (ref "U11") (pin "10") (pinfunction "ENT_10") (pintype "passive"))
      (node (ref "U11") (pin "16") (pinfunction "VCC_16") (pintype "passive"))
      (node (ref "U11") (pin "2") (pinfunction "CLK_2") (pintype "passive"))
      (node (ref "U11") (pin "7") (pinfunction "ENP_7") (pintype "passive"))
      (node (ref "U12") (pin "16") (pinfunction "VCC_16") (pintype "passive"))
      (node (ref "U12") (pin "3") (pinfunction "LT#_3") (pintype "passive"))
      (node (ref "U12") (pin "4") (pinfunction "BI#_4") (pintype "passive"))
      (node (ref "U13") (pin "1") (pinfunction "CLR#_1") (pintype "passive"))
      (node (ref "U13") (pin "10") (pinfunction "ENT_10") (pintype "passive"))
      (node (ref "U13") (pin "16") (pinfunction "VCC_16") (pintype "passive"))
      (node (ref "U13") (pin "7") (pinfunction "ENP_7") (pintype "passive"))
      (node (ref "U14") (pin "11") (pinfunction "4Y_11") (pintype "passive"))
      (node (ref "U14") (pin "14") (pinfunction "VCC_14") (pintype "passive"))
      (node (ref "U15") (pin "12") (pinfunction "4A_12") (pintype "passive"))
      (node (ref "U15") (pin "14") (pinfunction "VCC_14") (pintype "passive"))
      (node (ref "U16") (pin "16") (pinfunction "VDD_16") (pintype "passive"))
      (node (ref "U17") (pin "14") (pinfunction "VCC_14") (pintype "passive"))
      (node (ref "U17") (pin "4") (pinfunction "1PRE#_4") (pintype "passive"))
      (node (ref "U17") (pin "5") (pinfunction "1Q_5") (pintype "passive"))
      (node (ref "U2") (pin "1") (pinfunction "CLR#_1") (pintype "passive"))
      (node (ref "U2") (pin "10") (pinfunction "ENT_10") (pintype "passive"))
      (node (ref "U2") (pin "16") (pinfunction "VCC_16") (pintype "passive"))
      (node (ref "U2") (pin "2") (pinfunction "CLK_2") (pintype "passive"))
      (node (ref "U2") (pin "7") (pinfunction "ENP_7") (pintype "passive"))
      (node (ref "U3") (pin "11") (pinfunction "4Y_11") (pintype "passive"))
      (node (ref "U3") (pin "14") (pinfunction "VCC_14") (pintype "passive"))
      (node (ref "U3") (pin "6") (pinfunction "2Y_6") (pintype "passive"))
      (node (ref "U4") (pin "16") (pinfunction "VCC_16") (pintype "passive"))
      (node (ref "U4") (pin "3") (pinfunction "LT#_3") (pintype "passive"))
      (node (ref "U4") (pin "4") (pinfunction "BI#_4") (pintype "passive"))
      (node (ref "U5") (pin "1") (pinfunction "CLR#_1") (pintype "passive"))
      (node (ref "U5") (pin "10") (pinfunction "ENT_10") (pintype "passive"))
      (node (ref "U5") (pin "16") (pinfunction "VCC_16") (pintype "passive"))
      (node (ref "U5") (pin "7") (pinfunction "ENP_7") (pintype "passive"))
      (node (ref "U5") (pin "9") (pinfunction "LOAD#_9") (pintype "passive"))
      (node (ref "U6") (pin "16") (pinfunction "VCC_16") (pintype "passive"))
      (node (ref "U6") (pin "3") (pinfunction "LT#_3") (pintype "passive"))
      (node (ref "U6") (pin "4") (pinfunction "BI#_4") (pintype "passive"))
      (node (ref "U7") (pin "1") (pinfunction "CLR#_1") (pintype "passive"))
      (node (ref "U7") (pin "10") (pinfunction "ENT_10") (pintype "passive"))
      (node (ref "U7") (pin "16") (pinfunction "VCC_16") (pintype "passive"))
      (node (ref "U7") (pin "2") (pinfunction "CLK_2") (pintype "passive"))
      (node (ref "U7") (pin "7") (pinfunction "ENP_7") (pintype "passive"))
      (node (ref "U8") (pin "16") (pinfunction "VCC_16") (pintype "passive"))
      (node (ref "U8") (pin "3") (pinfunction "LT#_3") (pintype "passive"))
      (node (ref "U8") (pin "4") (pinfunction "BI#_4") (pintype "passive"))
      (node (ref "U9") (pin "1") (pinfunction "CLR#_1") (pintype "passive"))
      (node (ref "U9") (pin "10") (pinfunction "ENT_10") (pintype "passive"))
      (node (ref "U9") (pin "16") (pinfunction "VCC_16") (pintype "passive"))
      (node (ref "U9") (pin "7") (pinfunction "ENP_7") (pintype "passive"))
      (node (ref "U9") (pin "9") (pinfunction "LOAD#_9") (pintype "passive"))
    )
    (net (code "111") (name "unconnected-(DS1-DP-Pad5)") (class "Default")
      (node (ref "DS1") (pin "5") (pinfunction "DP_5") (pintype "passive"))
    )
    (net (code "112") (name "unconnected-(DS2-DP-Pad5)") (class "Default")
      (node (ref "DS2") (pin "5") (pinfunction "DP_5") (pintype "passive"))
    )
    (net (code "113") (name "unconnected-(DS3-DP-Pad5)") (class "Default")
      (node (ref "DS3") (pin "5") (pinfunction "DP_5") (pintype "passive"))
    )
    (net (code "114") (name "unconnected-(DS4-DP-Pad5)") (class "Default")
      (node (ref "DS4") (pin "5") (pinfunction "DP_5") (pintype "passive"))
    )
    (net (code "115") (name "unconnected-(DS5-DP-Pad5)") (class "Default")
      (node (ref "DS5") (pin "5") (pinfunction "DP_5") (pintype "passive"))
    )
    (net (code "116") (name "unconnected-(DS6-DP-Pad5)") (class "Default")
      (node (ref "DS6") (pin "5") (pinfunction "DP_5") (pintype "passive"))
    )
    (net (code "117") (name "unconnected-(KEY-Pad3)") (class "Default")
      (node (ref "KEY") (pin "3") (pinfunction "3_3") (pintype "passive"))
    )
    (net (code "118") (name "unconnected-(KEY-Pad4)") (class "Default")
      (node (ref "KEY") (pin "4") (pinfunction "4_4") (pintype "passive"))
    )
    (net (code "119") (name "unconnected-(KEY-Pad5)") (class "Default")
      (node (ref "KEY") (pin "5") (pinfunction "5_5") (pintype "passive"))
    )
    (net (code "120") (name "unconnected-(KEY-Pad6)") (class "Default")
      (node (ref "KEY") (pin "6") (pinfunction "6_6") (pintype "passive"))
    )
    (net (code "121") (name "unconnected-(RP1-Pad8)") (class "Default")
      (node (ref "RP1") (pin "8") (pinfunction "8_8") (pintype "passive"))
    )
    (net (code "122") (name "unconnected-(RP1-Pad9)") (class "Default")
      (node (ref "RP1") (pin "9") (pinfunction "9_9") (pintype "passive"))
    )
    (net (code "123") (name "unconnected-(RP2-Pad8)") (class "Default")
      (node (ref "RP2") (pin "8") (pinfunction "8_8") (pintype "passive"))
    )
    (net (code "124") (name "unconnected-(RP2-Pad9)") (class "Default")
      (node (ref "RP2") (pin "9") (pinfunction "9_9") (pintype "passive"))
    )
    (net (code "125") (name "unconnected-(RP3-Pad8)") (class "Default")
      (node (ref "RP3") (pin "8") (pinfunction "8_8") (pintype "passive"))
    )
    (net (code "126") (name "unconnected-(RP3-Pad9)") (class "Default")
      (node (ref "RP3") (pin "9") (pinfunction "9_9") (pintype "passive"))
    )
    (net (code "127") (name "unconnected-(RP4-Pad8)") (class "Default")
      (node (ref "RP4") (pin "8") (pinfunction "8_8") (pintype "passive"))
    )
    (net (code "128") (name "unconnected-(RP4-Pad9)") (class "Default")
      (node (ref "RP4") (pin "9") (pinfunction "9_9") (pintype "passive"))
    )
    (net (code "129") (name "unconnected-(RP5-Pad8)") (class "Default")
      (node (ref "RP5") (pin "8") (pinfunction "8_8") (pintype "passive"))
    )
    (net (code "130") (name "unconnected-(RP5-Pad9)") (class "Default")
      (node (ref "RP5") (pin "9") (pinfunction "9_9") (pintype "passive"))
    )
    (net (code "131") (name "unconnected-(RP6-Pad8)") (class "Default")
      (node (ref "RP6") (pin "8") (pinfunction "8_8") (pintype "passive"))
    )
    (net (code "132") (name "unconnected-(RP6-Pad9)") (class "Default")
      (node (ref "RP6") (pin "9") (pinfunction "9_9") (pintype "passive"))
    )
    (net (code "133") (name "unconnected-(U2-ROC-Pad15)") (class "Default")
      (node (ref "U2") (pin "15") (pinfunction "ROC_15") (pintype "passive"))
    )
    (net (code "134") (name "unconnected-(U5-ROC-Pad15)") (class "Default")
      (node (ref "U5") (pin "15") (pinfunction "ROC_15") (pintype "passive"))
    )
    (net (code "135") (name "unconnected-(U7-ROC-Pad15)") (class "Default")
      (node (ref "U7") (pin "15") (pinfunction "ROC_15") (pintype "passive"))
    )
    (net (code "136") (name "unconnected-(U9-ROC-Pad15)") (class "Default")
      (node (ref "U9") (pin "15") (pinfunction "ROC_15") (pintype "passive"))
    )
    (net (code "137") (name "unconnected-(U11-ROC-Pad15)") (class "Default")
      (node (ref "U11") (pin "15") (pinfunction "ROC_15") (pintype "passive"))
    )
    (net (code "138") (name "unconnected-(U13-ROC-Pad15)") (class "Default")
      (node (ref "U13") (pin "15") (pinfunction "ROC_15") (pintype "passive"))
    )
    (net (code "139") (name "unconnected-(U14-3A-Pad10)") (class "Default")
      (node (ref "U14") (pin "10") (pinfunction "3A_10") (pintype "passive"))
    )
    (net (code "140") (name "unconnected-(U14-3B-Pad9)") (class "Default")
      (node (ref "U14") (pin "9") (pinfunction "3B_9") (pintype "passive"))
    )
    (net (code "141") (name "unconnected-(U14-3Y-Pad8)") (class "Default")
      (node (ref "U14") (pin "8") (pinfunction "3Y_8") (pintype "passive"))
    )
    (net (code "142") (name "unconnected-(U15-3A-Pad9)") (class "Default")
      (node (ref "U15") (pin "9") (pinfunction "3A_9") (pintype "passive"))
    )
    (net (code "143") (name "unconnected-(U15-3B-Pad10)") (class "Default")
      (node (ref "U15") (pin "10") (pinfunction "3B_10") (pintype "passive"))
    )
    (net (code "144") (name "unconnected-(U15-3Y-Pad8)") (class "Default")
      (node (ref "U15") (pin "8") (pinfunction "3Y_8") (pintype "passive"))
    )
    (net (code "145") (name "unconnected-(U16--0-Pad9)") (class "Default")
      (node (ref "U16") (pin "9") (pinfunction "-0_9") (pintype "passive"))
    )
    (net (code "146") (name "unconnected-(U16-Q4-Pad7)") (class "Default")
      (node (ref "U16") (pin "7") (pinfunction "Q4_7") (pintype "passive"))
    )
    (net (code "147") (name "unconnected-(U16-Q5-Pad5)") (class "Default")
      (node (ref "U16") (pin "5") (pinfunction "Q5_5") (pintype "passive"))
    )
    (net (code "148") (name "unconnected-(U16-Q6-Pad4)") (class "Default")
      (node (ref "U16") (pin "4") (pinfunction "Q6_4") (pintype "passive"))
    )
    (net (code "149") (name "unconnected-(U16-Q7-Pad6)") (class "Default")
      (node (ref "U16") (pin "6") (pinfunction "Q7_6") (pintype "passive"))
    )
    (net (code "150") (name "unconnected-(U16-Q8-Pad14)") (class "Default")
      (node (ref "U16") (pin "14") (pinfunction "Q8_14") (pintype "passive"))
    )
    (net (code "151") (name "unconnected-(U16-Q9-Pad13)") (class "Default")
      (node (ref "U16") (pin "13") (pinfunction "Q9_13") (pintype "passive"))
    )
    (net (code "152") (name "unconnected-(U16-Q10-Pad15)") (class "Default")
      (node (ref "U16") (pin "15") (pinfunction "Q10_15") (pintype "passive"))
    )
    (net (code "153") (name "unconnected-(U16-Q12-Pad1)") (class "Default")
      (node (ref "U16") (pin "1") (pinfunction "Q12_1") (pintype "passive"))
    )
    (net (code "154") (name "unconnected-(U16-Q13-Pad2)") (class "Default")
      (node (ref "U16") (pin "2") (pinfunction "Q13_2") (pintype "passive"))
    )
    (net (code "155") (name "unconnected-(U17-1CLR#-Pad1)") (class "Default")
      (node (ref "U17") (pin "1") (pinfunction "1CLR#_1") (pintype "passive"))
    )
    (net (code "156") (name "unconnected-(U17-2CLK-Pad11)") (class "Default")
      (node (ref "U17") (pin "11") (pinfunction "2CLK_11") (pintype "passive"))
    )
    (net (code "157") (name "unconnected-(U17-2CLR#-Pad13)") (class "Default")
      (node (ref "U17") (pin "13") (pinfunction "2CLR#_13") (pintype "passive"))
    )
    (net (code "158") (name "unconnected-(U17-2D-Pad12)") (class "Default")
      (node (ref "U17") (pin "12") (pinfunction "2D_12") (pintype "passive"))
    )
    (net (code "159") (name "unconnected-(U17-2PRE#-Pad10)") (class "Default")
      (node (ref "U17") (pin "10") (pinfunction "2PRE#_10") (pintype "passive"))
    )
    (net (code "160") (name "unconnected-(U17-2Q#-Pad8)") (class "Default")
      (node (ref "U17") (pin "8") (pinfunction "2Q#_8") (pintype "passive"))
    )
    (net (code "161") (name "unconnected-(U17-2Q-Pad9)") (class "Default")
      (node (ref "U17") (pin "9") (pinfunction "2Q_9") (pintype "passive"))
    )
  )
)
